# FRONT-UNIT-WIDE.net
KiCad netlist of a schematic drawn in Altium Designer
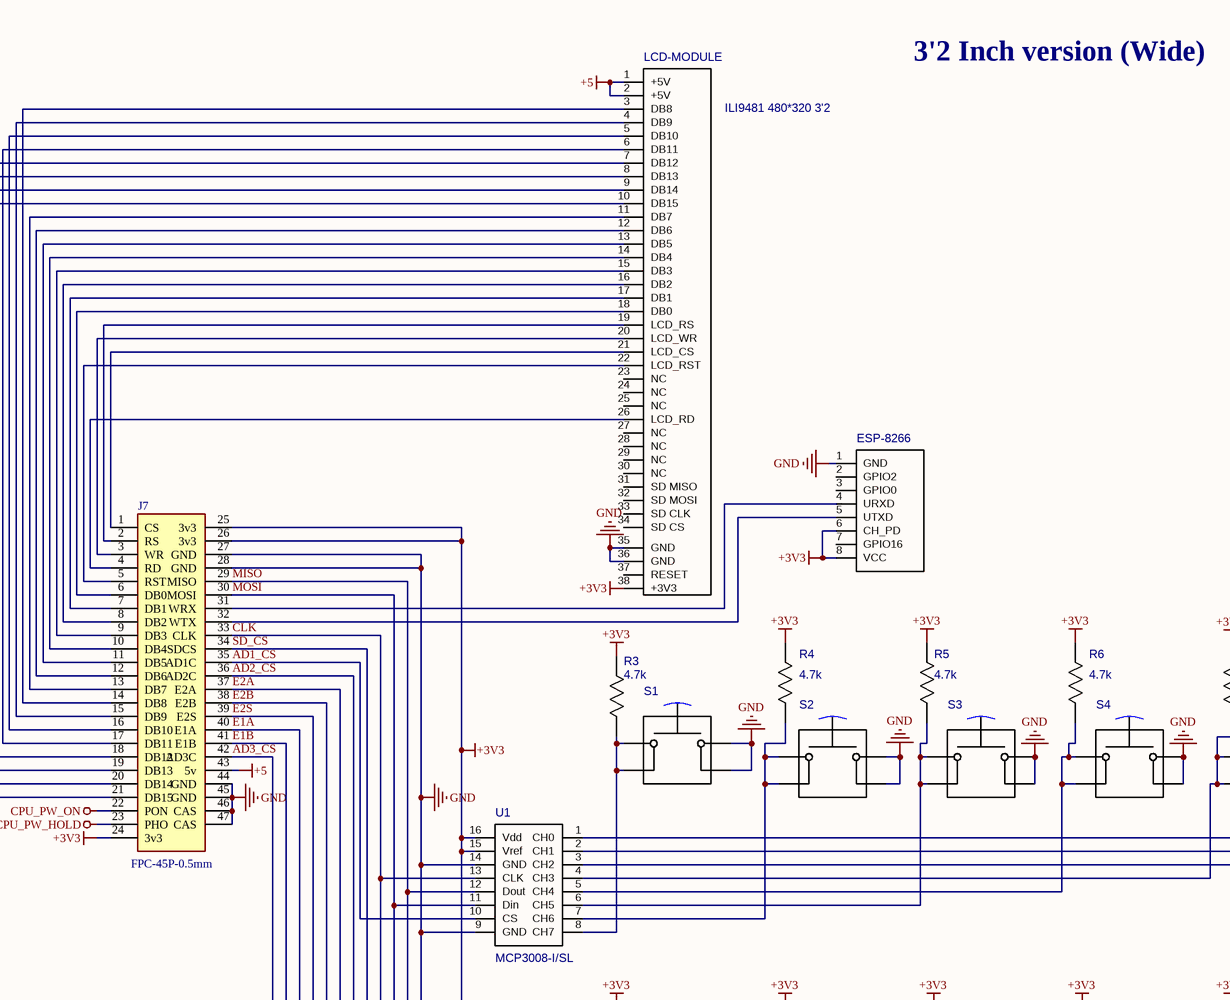
[diagram p0: FRONT-UNIT-WIDE.SCHDOC, top left]
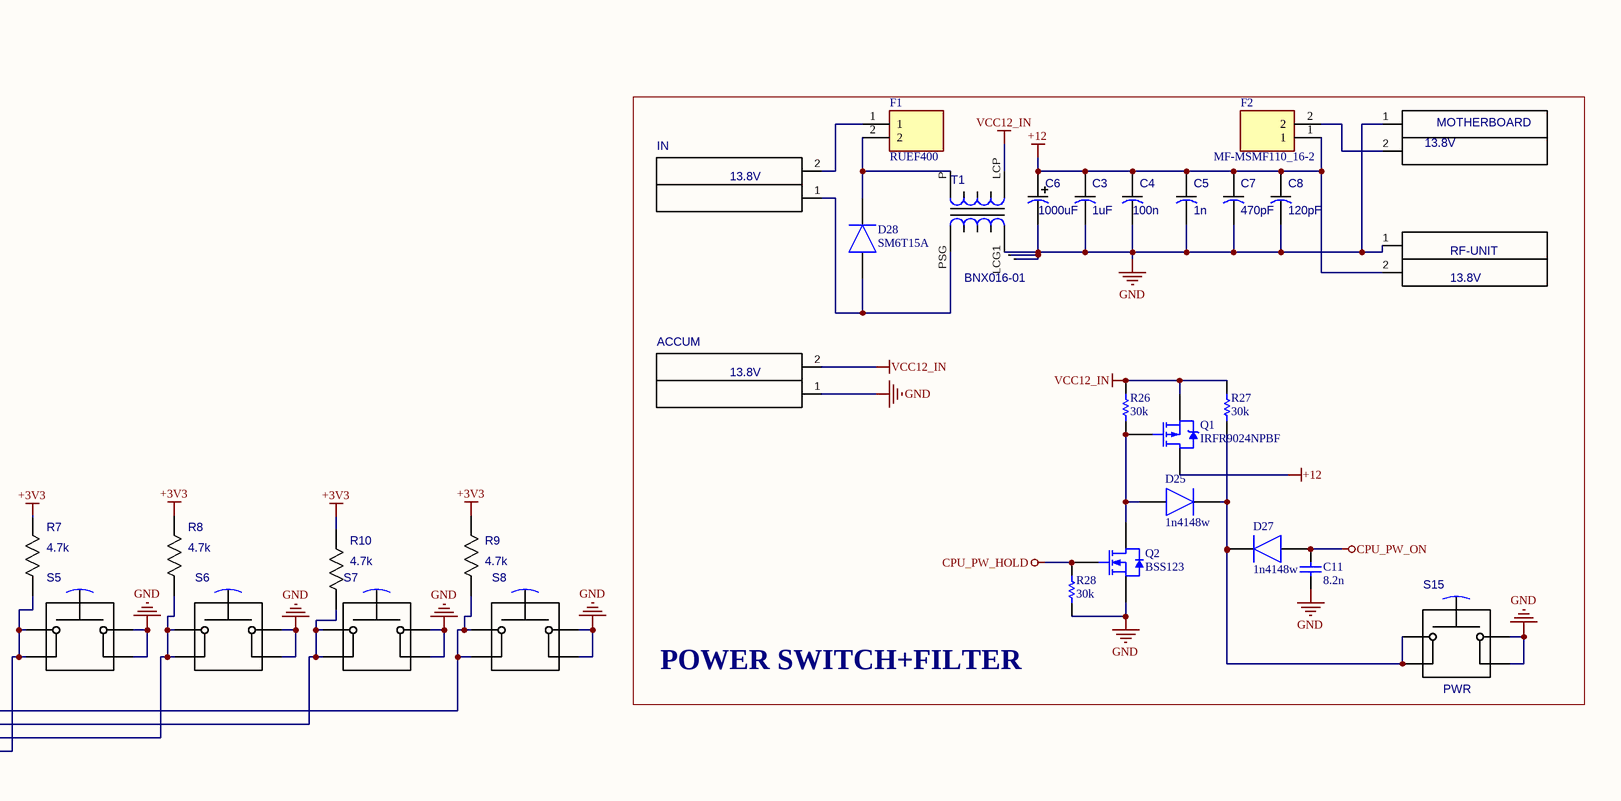
[diagram p1: FRONT-UNIT-WIDE.SCHDOC, top right]
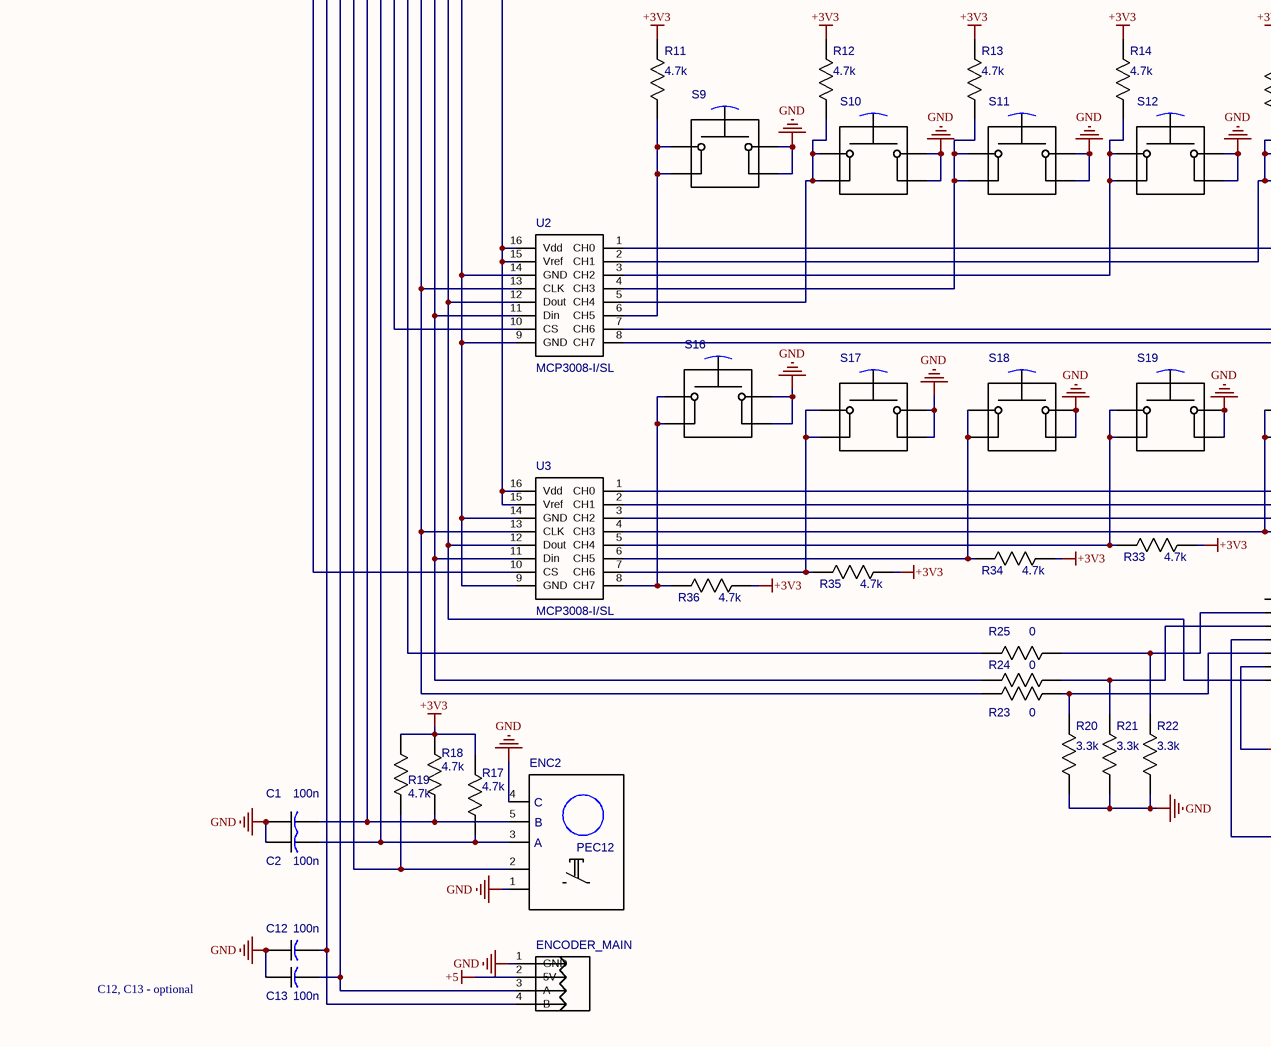
[diagram p2: FRONT-UNIT-WIDE.SCHDOC, bottom left]
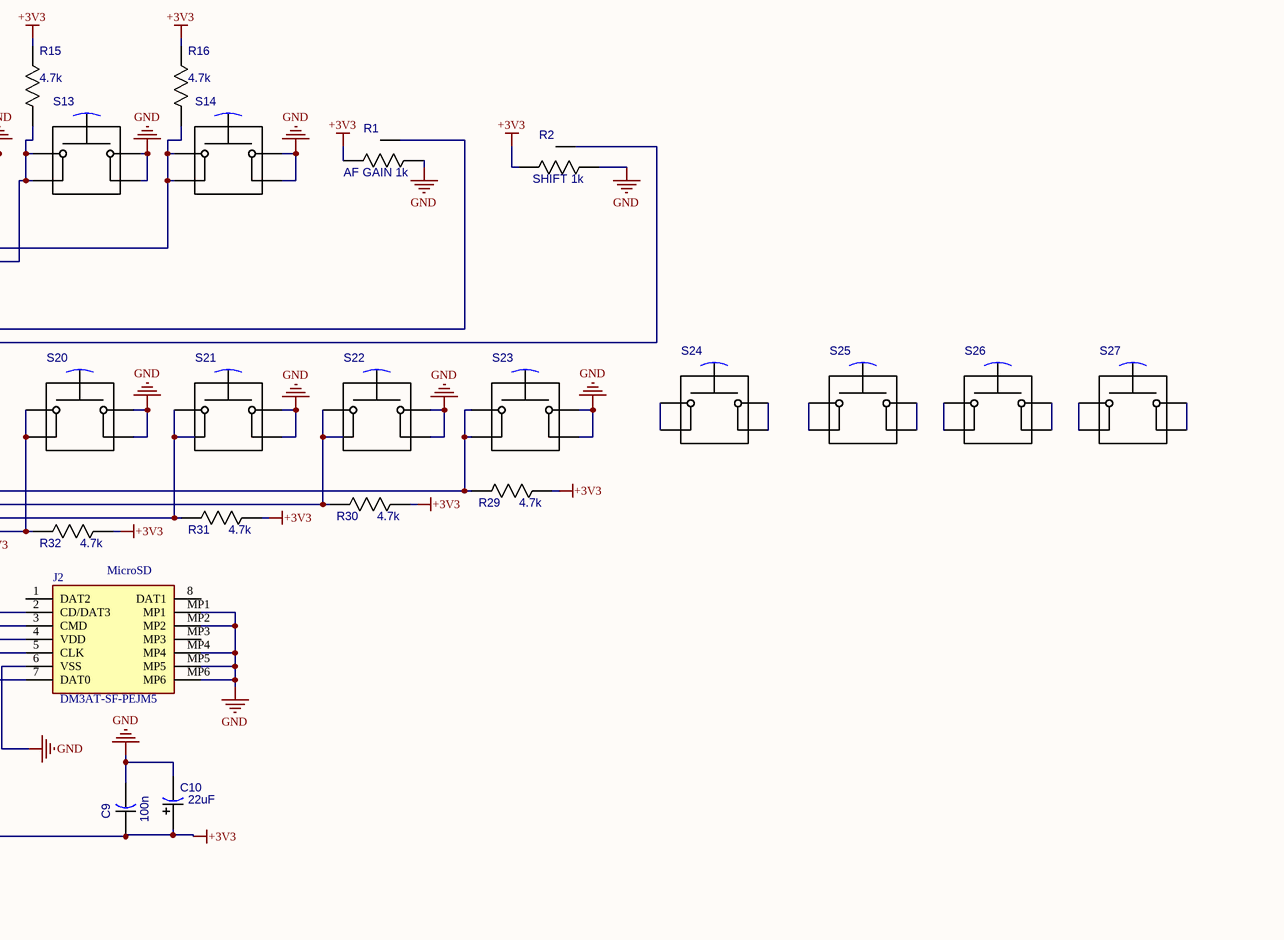
[diagram p3: FRONT-UNIT-WIDE.SCHDOC, bottom right]

(export (version "E")
  (design (tool "Eeschema 10.0.6"))
  (components
    (comp (ref "ACCUM")
      (value "13.8V")
      (footprint "JX2")
      (description "JX2")
      (libsource (lib "*") (part "JX2"))
    )
    (comp (ref "C1")
      (value "100n")
      (footprint "CAP_0805")
      (description "CAP_0805")
      (libsource (lib "*") (part "CAP_0805"))
    )
    (comp (ref "C2")
      (value "100n")
      (footprint "CAP_0805")
      (description "CAP_0805")
      (libsource (lib "*") (part "CAP_0805"))
    )
    (comp (ref "C3")
      (value "1uF")
      (footprint "CAP_1206")
      (description "CAP_1206")
      (libsource (lib "*") (part "CAP_1206"))
    )
    (comp (ref "C4")
      (value "100n")
      (footprint "CAP_1206")
      (description "CAP_1206")
      (libsource (lib "*") (part "CAP_1206"))
    )
    (comp (ref "C5")
      (value "1n")
      (footprint "CAP_1206")
      (description "CAP_1206")
      (libsource (lib "*") (part "CAP_1206"))
    )
    (comp (ref "C6")
      (value "1000uF")
      (footprint "CAP250RP")
      (description "CAP250RP")
      (libsource (lib "*") (part "CAP250RP"))
    )
    (comp (ref "C7")
      (value "470pF")
      (footprint "CAP_1206")
      (description "CAP_1206")
      (libsource (lib "*") (part "CAP_1206"))
    )
    (comp (ref "C8")
      (value "120pF")
      (footprint "CAP_1206")
      (description "CAP_1206")
      (libsource (lib "*") (part "CAP_1206"))
    )
    (comp (ref "C9")
      (value "100n")
      (footprint "CAP_0805")
      (description "CAP_0805")
      (libsource (lib "*") (part "CAP_0805"))
    )
    (comp (ref "C10")
      (value "22uF")
      (footprint "EEEFC_sizeB")
      (description "EEEFC_sizeB")
      (libsource (lib "*") (part "EEEFC_sizeB"))
    )
    (comp (ref "C11")
      (value "8.2n")
      (footprint "CAPC2013X94X50LL20T25")
      (description "CAP_1206")
      (fields
        (field (name "MANUFACTURER") "AVX Interconnect / Elco")
        (field (name "PART NUMBER") "08055C822KAT2A")
      )
      (libsource (lib "Altium Content Vault") (part "CAP"))
    )
    (comp (ref "C12")
      (value "100n")
      (footprint "CAP_0805")
      (description "CAP_0805")
      (libsource (lib "*") (part "CAP_0805"))
    )
    (comp (ref "C13")
      (value "100n")
      (footprint "CAP_0805")
      (description "CAP_0805")
      (libsource (lib "*") (part "CAP_0805"))
    )
    (comp (ref "D25")
      (value "1n4148w")
      (footprint "SamacSys:SOD3716X135N")
      (description "Diode")
      (libsource (lib "*") (part "1n4148w"))
    )
    (comp (ref "D27")
      (value "1n4148w")
      (footprint "SamacSys:SOD3716X135N")
      (description "Diode")
      (libsource (lib "*") (part "1n4148w"))
    )
    (comp (ref "D28")
      (value "SM6T15A")
      (footprint "SamacSys:SMBJ36CATR")
      (description "Diode")
      (fields (field (name "MOUSER PART NUMBER") "511-SM6T15A") (field (name "RS PART NUMBER") "4864915P"))
      (libsource (lib "*") (part "SM6T15A"))
    )
    (comp (ref "ENC2") (value "PEC12") (footprint "PEC12") (libsource (lib "*") (part "PEC12")))
    (comp (ref "ENCODER_MAIN")
      (value "OPTICAL ENCODER")
      (footprint "644456-4")
      (libsource (lib "*") (part "644456-4"))
    )
    (comp (ref "ESP-8266")
      (value "ESP-01 ESP8266")
      (footprint "ESP-01 ESP8266")
      (libsource (lib "*") (part "ESP-01 ESP8266"))
    )
    (comp (ref "F1")
      (value "RUEF400")
      (footprint "SamacSys:RUEF400")
      (description "Fuse")
      (fields (field (name "MOUSER PART NUMBER") "650-RUEF400") (field (name "RS PART NUMBER") "5176837P"))
      (libsource (lib "*") (part "RUEF400"))
    )
    (comp (ref "F2")
      (value "MF-MSMF110_16-2")
      (footprint "SamacSys:FUSC4632X85N")
      (description "Fuse")
      (fields
        (field (name "MANUFACTURER_PART_NUMBER") "MF-MSMF110/16-2")
        (field (name "MOUSER PART NUMBER") "652-MF-MSMF110/16-2")
      )
      (libsource (lib "*") (part "MF-MSMF110_16-2"))
    )
    (comp (ref "IN") (value "13.8V") (footprint "JX2") (description "JX2") (libsource (lib "*") (part "JX2")))
    (comp (ref "J2")
      (value "DM3AT-SF-PEJM5")
      (footprint "SamacSys:DM3ATSFPEJM5")
      (description "Connector")
      (libsource (lib "*") (part "DM3AT-SF-PEJM5"))
    )
    (comp (ref "J7")
      (value "FPC-45P-0.5mm")
      (footprint "FRONT-UNIT-WIDE:FH12S45S05SH60")
      (description "Connector")
      (fields
        (field (name "MANUFACTURER_PART_NUMBER") "FH12S-45S-0.5SH(55)")
        (field (name "MOUSER PART NUMBER") "798-FH12S-45S-05SH55")
      )
      (libsource (lib "*") (part "FH12S-45S-0.5SH_55_"))
    )
    (comp (ref "LCD-MODULE")
      (value "ILI9481 480*320 3'2")
      (footprint "LCD-MODULE-3.2-480-320")
      (description "LCD-MODULE_3'2_480х320")
      (libsource (lib "FRONT-UNIT") (part "LCD-MODULE_3'2_480х320"))
    )
    (comp (ref "MOTHERBOARD")
      (value "13.8V")
      (footprint "JX2")
      (description "JX2")
      (libsource (lib "*") (part "JX2"))
    )
    (comp (ref "Q1")
      (value "IRFR9024NPBF")
      (footprint "ONSC-DPAK-3-369C-01_V")
      (description "IRFR9024NPBF, Транзистор, Р-канал 55В 11А")
      (fields (field (name "MANUFACTURER") "On Semiconductor") (field (name "PARTNUMBER") "NTD2955G"))
      (libsource (lib "Altium Content Vault") (part "ONSC-PMOS-G1S3D4-3_B"))
    )
    (comp (ref "Q2")
      (value "BSS123")
      (footprint "FAIR-SOT23-3_V")
      (fields (field (name "MANUFACTURER") "Fairchild"))
      (libsource (lib "Altium Content Vault") (part "NEMOS-GSD-3"))
    )
    (comp (ref "R1")
      (value "AF GAIN 1k")
      (footprint "PTV09")
      (description "Adjustable Resistor PTV09")
      (fields (field (name "Comment") "ptv09a-4225f-b102"))
      (libsource (lib "*") (part "PTV09"))
    )
    (comp (ref "R2")
      (value "SHIFT 1k")
      (footprint "PTV09")
      (description "Adjustable Resistor PTV09")
      (fields (field (name "Comment") "ptv09a-4225f-b102"))
      (libsource (lib "*") (part "PTV09"))
    )
    (comp (ref "R3")
      (value "4.7k")
      (footprint "RES_0805")
      (description "RES_0805")
      (libsource (lib "*") (part "RES_0805"))
    )
    (comp (ref "R4")
      (value "4.7k")
      (footprint "RES_0805")
      (description "RES_0805")
      (libsource (lib "*") (part "RES_0805"))
    )
    (comp (ref "R5")
      (value "4.7k")
      (footprint "RES_0805")
      (description "RES_0805")
      (libsource (lib "*") (part "RES_0805"))
    )
    (comp (ref "R6")
      (value "4.7k")
      (footprint "RES_0805")
      (description "RES_0805")
      (libsource (lib "*") (part "RES_0805"))
    )
    (comp (ref "R7")
      (value "4.7k")
      (footprint "RES_0805")
      (description "RES_0805")
      (libsource (lib "*") (part "RES_0805"))
    )
    (comp (ref "R8")
      (value "4.7k")
      (footprint "RES_0805")
      (description "RES_0805")
      (libsource (lib "*") (part "RES_0805"))
    )
    (comp (ref "R9")
      (value "4.7k")
      (footprint "RES_0805")
      (description "RES_0805")
      (libsource (lib "*") (part "RES_0805"))
    )
    (comp (ref "R10")
      (value "4.7k")
      (footprint "RES_0805")
      (description "RES_0805")
      (libsource (lib "*") (part "RES_0805"))
    )
    (comp (ref "R11")
      (value "4.7k")
      (footprint "RES_0805")
      (description "RES_0805")
      (libsource (lib "*") (part "RES_0805"))
    )
    (comp (ref "R12")
      (value "4.7k")
      (footprint "RES_0805")
      (description "RES_0805")
      (libsource (lib "*") (part "RES_0805"))
    )
    (comp (ref "R13")
      (value "4.7k")
      (footprint "RES_0805")
      (description "RES_0805")
      (libsource (lib "*") (part "RES_0805"))
    )
    (comp (ref "R14")
      (value "4.7k")
      (footprint "RES_0805")
      (description "RES_0805")
      (libsource (lib "*") (part "RES_0805"))
    )
    (comp (ref "R15")
      (value "4.7k")
      (footprint "RES_0805")
      (description "RES_0805")
      (libsource (lib "*") (part "RES_0805"))
    )
    (comp (ref "R16")
      (value "4.7k")
      (footprint "RES_0805")
      (description "RES_0805")
      (libsource (lib "*") (part "RES_0805"))
    )
    (comp (ref "R17")
      (value "4.7k")
      (footprint "RES_0805")
      (description "RES_0805")
      (libsource (lib "*") (part "RES_0805"))
    )
    (comp (ref "R18")
      (value "4.7k")
      (footprint "RES_0805")
      (description "RES_0805")
      (libsource (lib "*") (part "RES_0805"))
    )
    (comp (ref "R19")
      (value "4.7k")
      (footprint "RES_0805")
      (description "RES_0805")
      (libsource (lib "*") (part "RES_0805"))
    )
    (comp (ref "R20")
      (value "3.3k")
      (footprint "RES_0805")
      (description "RES_0805")
      (libsource (lib "*") (part "RES_0805"))
    )
    (comp (ref "R21")
      (value "3.3k")
      (footprint "RES_0805")
      (description "RES_0805")
      (libsource (lib "*") (part "RES_0805"))
    )
    (comp (ref "R22")
      (value "3.3k")
      (footprint "RES_0805")
      (description "RES_0805")
      (libsource (lib "*") (part "RES_0805"))
    )
    (comp (ref "R23")
      (value "0")
      (footprint "RES_0805")
      (description "RES_0805")
      (libsource (lib "*") (part "RES_0805"))
    )
    (comp (ref "R24")
      (value "0")
      (footprint "RES_0805")
      (description "RES_0805")
      (libsource (lib "*") (part "RES_0805"))
    )
    (comp (ref "R25")
      (value "0")
      (footprint "RES_0805")
      (description "RES_0805")
      (libsource (lib "*") (part "RES_0805"))
    )
    (comp (ref "R26")
      (value "30k")
      (footprint "RESC2013X60X40NL20T25")
      (description "RES_0805")
      (fields (field (name "MANUFACTURER") "Panasonic") (field (name "PART NUMBER") "ERA-6AEB303V"))
      (libsource (lib "Altium Content Vault") (part "RES"))
    )
    (comp (ref "R27")
      (value "30k")
      (footprint "RESC2013X60X40NL20T25")
      (description "RES_0805")
      (fields (field (name "MANUFACTURER") "Panasonic") (field (name "PART NUMBER") "ERA-6AEB303V"))
      (libsource (lib "Altium Content Vault") (part "RES"))
    )
    (comp (ref "R28")
      (value "30k")
      (footprint "RESC2013X60X40NL20T25")
      (description "RES_0805")
      (fields (field (name "MANUFACTURER") "Panasonic") (field (name "PART NUMBER") "ERA-6AEB303V"))
      (libsource (lib "Altium Content Vault") (part "RES"))
    )
    (comp (ref "R29")
      (value "4.7k")
      (footprint "RES_0805")
      (description "RES_0805")
      (libsource (lib "*") (part "RES_0805"))
    )
    (comp (ref "R30")
      (value "4.7k")
      (footprint "RES_0805")
      (description "RES_0805")
      (libsource (lib "*") (part "RES_0805"))
    )
    (comp (ref "R31")
      (value "4.7k")
      (footprint "RES_0805")
      (description "RES_0805")
      (libsource (lib "*") (part "RES_0805"))
    )
    (comp (ref "R32")
      (value "4.7k")
      (footprint "RES_0805")
      (description "RES_0805")
      (libsource (lib "*") (part "RES_0805"))
    )
    (comp (ref "R33")
      (value "4.7k")
      (footprint "RES_0805")
      (description "RES_0805")
      (libsource (lib "*") (part "RES_0805"))
    )
    (comp (ref "R34")
      (value "4.7k")
      (footprint "RES_0805")
      (description "RES_0805")
      (libsource (lib "*") (part "RES_0805"))
    )
    (comp (ref "R35")
      (value "4.7k")
      (footprint "RES_0805")
      (description "RES_0805")
      (libsource (lib "*") (part "RES_0805"))
    )
    (comp (ref "R36")
      (value "4.7k")
      (footprint "RES_0805")
      (description "RES_0805")
      (libsource (lib "*") (part "RES_0805"))
    )
    (comp (ref "RF-UNIT")
      (value "13.8V")
      (footprint "JX2")
      (description "JX2")
      (libsource (lib "*") (part "JX2"))
    )
    (comp (ref "S1")
      (value "PTS645SK50LFS")
      (footprint "PTS645SK50LFS")
      (fields (field (name "LCSC PART #") "test"))
      (libsource (lib "*") (part "PTS645SK50LFS"))
    )
    (comp (ref "S2")
      (value "PTS645SK50LFS")
      (footprint "PTS645SK50LFS")
      (libsource (lib "*") (part "PTS645SK50LFS"))
    )
    (comp (ref "S3")
      (value "PTS645SK50LFS")
      (footprint "PTS645SK50LFS")
      (libsource (lib "*") (part "PTS645SK50LFS"))
    )
    (comp (ref "S4")
      (value "PTS645SK50LFS")
      (footprint "PTS645SK50LFS")
      (libsource (lib "*") (part "PTS645SK50LFS"))
    )
    (comp (ref "S5")
      (value "PTS645SK50LFS")
      (footprint "PTS645SK50LFS")
      (libsource (lib "*") (part "PTS645SK50LFS"))
    )
    (comp (ref "S6")
      (value "PTS645SK50LFS")
      (footprint "PTS645SK50LFS")
      (libsource (lib "*") (part "PTS645SK50LFS"))
    )
    (comp (ref "S7")
      (value "PTS645SK50LFS")
      (footprint "PTS645SK50LFS")
      (libsource (lib "*") (part "PTS645SK50LFS"))
    )
    (comp (ref "S8")
      (value "PTS645SK50LFS")
      (footprint "PTS645SK50LFS")
      (libsource (lib "*") (part "PTS645SK50LFS"))
    )
    (comp (ref "S9")
      (value "PTS645SK50LFS")
      (footprint "PTS645SK50LFS")
      (libsource (lib "*") (part "PTS645SK50LFS"))
    )
    (comp (ref "S10")
      (value "PTS645SK50LFS")
      (footprint "PTS645SK50LFS")
      (libsource (lib "*") (part "PTS645SK50LFS"))
    )
    (comp (ref "S11")
      (value "PTS645SK50LFS")
      (footprint "PTS645SK50LFS")
      (libsource (lib "*") (part "PTS645SK50LFS"))
    )
    (comp (ref "S12")
      (value "PTS645SK50LFS")
      (footprint "PTS645SK50LFS")
      (libsource (lib "*") (part "PTS645SK50LFS"))
    )
    (comp (ref "S13")
      (value "PTS645SK50LFS")
      (footprint "PTS645SK50LFS")
      (libsource (lib "*") (part "PTS645SK50LFS"))
    )
    (comp (ref "S14")
      (value "PTS645SK50LFS")
      (footprint "PTS645SK50LFS")
      (libsource (lib "*") (part "PTS645SK50LFS"))
    )
    (comp (ref "S15")
      (value "PWR")
      (footprint "PTS645SK50LFS")
      (description "PTS645SK50LFS")
      (libsource (lib "*") (part "PTS645SK50LFS"))
    )
    (comp (ref "S16")
      (value "PTS645SK50LFS")
      (footprint "PTS645SK50LFS")
      (libsource (lib "*") (part "PTS645SK50LFS"))
    )
    (comp (ref "S17")
      (value "PTS645SK50LFS")
      (footprint "PTS645SK50LFS")
      (libsource (lib "*") (part "PTS645SK50LFS"))
    )
    (comp (ref "S18")
      (value "PTS645SK50LFS")
      (footprint "PTS645SK50LFS")
      (libsource (lib "*") (part "PTS645SK50LFS"))
    )
    (comp (ref "S19")
      (value "PTS645SK50LFS")
      (footprint "PTS645SK50LFS")
      (libsource (lib "*") (part "PTS645SK50LFS"))
    )
    (comp (ref "S20")
      (value "PTS645SK50LFS")
      (footprint "PTS645SK50LFS")
      (libsource (lib "*") (part "PTS645SK50LFS"))
    )
    (comp (ref "S21")
      (value "PTS645SK50LFS")
      (footprint "PTS645SK50LFS")
      (libsource (lib "*") (part "PTS645SK50LFS"))
    )
    (comp (ref "S22")
      (value "PTS645SK50LFS")
      (footprint "PTS645SK50LFS")
      (libsource (lib "*") (part "PTS645SK50LFS"))
    )
    (comp (ref "S23")
      (value "PTS645SK50LFS")
      (footprint "PTS645SK50LFS")
      (libsource (lib "*") (part "PTS645SK50LFS"))
    )
    (comp (ref "S24")
      (value "PTS645SK50LFS")
      (footprint "PTS645SK50LFS")
      (libsource (lib "*") (part "PTS645SK50LFS"))
    )
    (comp (ref "S25")
      (value "PTS645SK50LFS")
      (footprint "PTS645SK50LFS")
      (libsource (lib "*") (part "PTS645SK50LFS"))
    )
    (comp (ref "S26")
      (value "PTS645SK50LFS")
      (footprint "PTS645SK50LFS")
      (libsource (lib "*") (part "PTS645SK50LFS"))
    )
    (comp (ref "S27")
      (value "PTS645SK50LFS")
      (footprint "PTS645SK50LFS")
      (libsource (lib "*") (part "PTS645SK50LFS"))
    )
    (comp (ref "T1")
      (value "BNX016-01")
      (footprint "TRANSF_ICORE")
      (libsource (lib "*") (part "TRANSF_ICORE"))
    )
    (comp (ref "U1")
      (value "MCP3008-I/SL")
      (footprint "MCP3008-I/SL")
      (libsource (lib "*") (part "MCP3008-I/SL"))
    )
    (comp (ref "U2")
      (value "MCP3008-I/SL")
      (footprint "MCP3008-I/SL")
      (libsource (lib "*") (part "MCP3008-I/SL"))
    )
    (comp (ref "U3")
      (value "MCP3008-I/SL")
      (footprint "MCP3008-I/SL")
      (libsource (lib "*") (part "MCP3008-I/SL"))
    )
  )
  (nets
    (net (code "1") (name "+3V3") (class "Default")
      (node (ref "C10") (pin "1") (pinfunction "PLUS_1") (pintype "passive"))
      (node (ref "C9") (pin "1") (pinfunction "1_1") (pintype "passive"))
      (node (ref "ESP-8266") (pin "6") (pinfunction "CH_PD_6") (pintype "passive"))
      (node (ref "ESP-8266") (pin "8") (pinfunction "VCC_8") (pintype "passive"))
      (node (ref "J2") (pin "4") (pinfunction "VDD_4") (pintype "passive"))
      (node (ref "J7") (pin "24") (pinfunction "3v3_24") (pintype "passive"))
      (node (ref "J7") (pin "25") (pinfunction "3v3_25") (pintype "passive"))
      (node (ref "J7") (pin "26") (pinfunction "3v3_26") (pintype "passive"))
      (node (ref "LCD-MODULE") (pin "38") (pinfunction "+3V3_38") (pintype "passive"))
      (node (ref "R1") (pin "1") (pinfunction "CW_1") (pintype "passive"))
      (node (ref "R10") (pin "2") (pinfunction "2_2") (pintype "passive"))
      (node (ref "R11") (pin "2") (pinfunction "2_2") (pintype "passive"))
      (node (ref "R12") (pin "2") (pinfunction "2_2") (pintype "passive"))
      (node (ref "R13") (pin "2") (pinfunction "2_2") (pintype "passive"))
      (node (ref "R14") (pin "2") (pinfunction "2_2") (pintype "passive"))
      (node (ref "R15") (pin "2") (pinfunction "2_2") (pintype "passive"))
      (node (ref "R16") (pin "2") (pinfunction "2_2") (pintype "passive"))
      (node (ref "R17") (pin "2") (pinfunction "2_2") (pintype "passive"))
      (node (ref "R18") (pin "2") (pinfunction "2_2") (pintype "passive"))
      (node (ref "R19") (pin "2") (pinfunction "2_2") (pintype "passive"))
      (node (ref "R2") (pin "1") (pinfunction "CW_1") (pintype "passive"))
      (node (ref "R29") (pin "2") (pinfunction "2_2") (pintype "passive"))
      (node (ref "R3") (pin "2") (pinfunction "2_2") (pintype "passive"))
      (node (ref "R30") (pin "2") (pinfunction "2_2") (pintype "passive"))
      (node (ref "R31") (pin "2") (pinfunction "2_2") (pintype "passive"))
      (node (ref "R32") (pin "2") (pinfunction "2_2") (pintype "passive"))
      (node (ref "R33") (pin "2") (pinfunction "2_2") (pintype "passive"))
      (node (ref "R34") (pin "2") (pinfunction "2_2") (pintype "passive"))
      (node (ref "R35") (pin "2") (pinfunction "2_2") (pintype "passive"))
      (node (ref "R36") (pin "2") (pinfunction "2_2") (pintype "passive"))
      (node (ref "R4") (pin "2") (pinfunction "2_2") (pintype "passive"))
      (node (ref "R5") (pin "2") (pinfunction "2_2") (pintype "passive"))
      (node (ref "R6") (pin "2") (pinfunction "2_2") (pintype "passive"))
      (node (ref "R7") (pin "2") (pinfunction "2_2") (pintype "passive"))
      (node (ref "R8") (pin "2") (pinfunction "2_2") (pintype "passive"))
      (node (ref "R9") (pin "2") (pinfunction "2_2") (pintype "passive"))
      (node (ref "U1") (pin "15") (pinfunction "Vref_15") (pintype "passive"))
      (node (ref "U1") (pin "16") (pinfunction "Vdd_16") (pintype "passive"))
      (node (ref "U2") (pin "15") (pinfunction "Vref_15") (pintype "passive"))
      (node (ref "U2") (pin "16") (pinfunction "Vdd_16") (pintype "passive"))
      (node (ref "U3") (pin "15") (pinfunction "Vref_15") (pintype "passive"))
      (node (ref "U3") (pin "16") (pinfunction "Vdd_16") (pintype "passive"))
    )
    (net (code "2") (name "+5") (class "Default")
      (node (ref "ENCODER_MAIN") (pin "2") (pinfunction "5V_2") (pintype "passive"))
      (node (ref "J7") (pin "43") (pinfunction "5v_43") (pintype "passive"))
      (node (ref "LCD-MODULE") (pin "1") (pinfunction "+5V_1") (pintype "passive"))
      (node (ref "LCD-MODULE") (pin "2") (pinfunction "+5V_2") (pintype "passive"))
    )
    (net (code "3") (name "+12") (class "Default")
      (node (ref "C3") (pin "1") (pinfunction "1_1") (pintype "passive"))
      (node (ref "C4") (pin "1") (pinfunction "1_1") (pintype "passive"))
      (node (ref "C5") (pin "1") (pinfunction "1_1") (pintype "passive"))
      (node (ref "C6") (pin "1") (pinfunction "PLUS_1") (pintype "passive"))
      (node (ref "C7") (pin "1") (pinfunction "1_1") (pintype "passive"))
      (node (ref "C8") (pin "1") (pinfunction "1_1") (pintype "passive"))
      (node (ref "F2") (pin "1") (pinfunction "1_1") (pintype "passive"))
      (node (ref "Q1") (pin "4") (pinfunction "D_4") (pintype "passive"))
      (node (ref "RF-UNIT") (pin "2") (pinfunction "2_2") (pintype "passive"))
    )
    (net (code "4") (name "/AD1_CS") (class "Default")
      (node (ref "J7") (pin "35") (pinfunction "AD1C_35") (pintype "passive"))
      (node (ref "U1") (pin "10") (pinfunction "CS_10") (pintype "passive"))
    )
    (net (code "5") (name "/AD2_CS") (class "Default")
      (node (ref "J7") (pin "36") (pinfunction "AD2C_36") (pintype "passive"))
      (node (ref "U2") (pin "10") (pinfunction "CS_10") (pintype "passive"))
    )
    (net (code "6") (name "/AD3_CS") (class "Default")
      (node (ref "J7") (pin "42") (pinfunction "AD3C_42") (pintype "passive"))
      (node (ref "U3") (pin "10") (pinfunction "CS_10") (pintype "passive"))
    )
    (net (code "7") (name "/CLK") (class "Default")
      (node (ref "J7") (pin "33") (pinfunction "CLK_33") (pintype "passive"))
      (node (ref "R23") (pin "2") (pinfunction "2_2") (pintype "passive"))
      (node (ref "U1") (pin "13") (pinfunction "CLK_13") (pintype "passive"))
      (node (ref "U2") (pin "13") (pinfunction "CLK_13") (pintype "passive"))
      (node (ref "U3") (pin "13") (pinfunction "CLK_13") (pintype "passive"))
    )
    (net (code "8") (name "/E1A") (class "Default")
      (node (ref "C13") (pin "2") (pinfunction "2_2") (pintype "passive"))
      (node (ref "ENCODER_MAIN") (pin "3") (pinfunction "A_3") (pintype "passive"))
      (node (ref "J7") (pin "40") (pinfunction "E1A_40") (pintype "passive"))
    )
    (net (code "9") (name "/E1B") (class "Default")
      (node (ref "C12") (pin "2") (pinfunction "2_2") (pintype "passive"))
      (node (ref "ENCODER_MAIN") (pin "4") (pinfunction "B_4") (pintype "passive"))
      (node (ref "J7") (pin "41") (pinfunction "E1B_41") (pintype "passive"))
    )
    (net (code "10") (name "/E2A") (class "Default")
      (node (ref "C2") (pin "2") (pinfunction "2_2") (pintype "passive"))
      (node (ref "ENC2") (pin "3") (pinfunction "A_3") (pintype "passive"))
      (node (ref "J7") (pin "37") (pinfunction "E2A_37") (pintype "passive"))
      (node (ref "R17") (pin "1") (pinfunction "1_1") (pintype "passive"))
    )
    (net (code "11") (name "/E2B") (class "Default")
      (node (ref "C1") (pin "2") (pinfunction "2_2") (pintype "passive"))
      (node (ref "ENC2") (pin "5") (pinfunction "B_5") (pintype "passive"))
      (node (ref "J7") (pin "38") (pinfunction "E2B_38") (pintype "passive"))
      (node (ref "R18") (pin "1") (pinfunction "1_1") (pintype "passive"))
    )
    (net (code "12") (name "/E2S") (class "Default")
      (node (ref "ENC2") (pin "2") (pinfunction "2_2") (pintype "passive"))
      (node (ref "J7") (pin "39") (pinfunction "E2S_39") (pintype "passive"))
      (node (ref "R19") (pin "1") (pinfunction "1_1") (pintype "passive"))
    )
    (net (code "13") (name "/MISO") (class "Default")
      (node (ref "J2") (pin "7") (pinfunction "DAT0_7") (pintype "passive"))
      (node (ref "J7") (pin "29") (pinfunction "MISO_29") (pintype "passive"))
      (node (ref "U1") (pin "12") (pinfunction "Dout_12") (pintype "passive"))
      (node (ref "U2") (pin "12") (pinfunction "Dout_12") (pintype "passive"))
      (node (ref "U3") (pin "12") (pinfunction "Dout_12") (pintype "passive"))
    )
    (net (code "14") (name "/MOSI") (class "Default")
      (node (ref "J7") (pin "30") (pinfunction "MOSI_30") (pintype "passive"))
      (node (ref "R24") (pin "2") (pinfunction "2_2") (pintype "passive"))
      (node (ref "U1") (pin "11") (pinfunction "Din_11") (pintype "passive"))
      (node (ref "U2") (pin "11") (pinfunction "Din_11") (pintype "passive"))
      (node (ref "U3") (pin "11") (pinfunction "Din_11") (pintype "passive"))
    )
    (net (code "15") (name "/SD_CS") (class "Default")
      (node (ref "J7") (pin "34") (pinfunction "SDCS_34") (pintype "passive"))
      (node (ref "R25") (pin "2") (pinfunction "2_2") (pintype "passive"))
    )
    (net (code "16") (name "CPU_PW_HOLD") (class "Default")
      (node (ref "J7") (pin "23") (pinfunction "PHO_23") (pintype "passive"))
      (node (ref "Q2") (pin "1") (pinfunction "G_1") (pintype "passive"))
      (node (ref "R28") (pin "2") (pinfunction "2_2") (pintype "passive"))
    )
    (net (code "17") (name "CPU_PW_ON") (class "Default")
      (node (ref "C11") (pin "2") (pinfunction "2_2") (pintype "passive"))
      (node (ref "D27") (pin "2") (pinfunction "A_2") (pintype "passive"))
      (node (ref "J7") (pin "22") (pinfunction "PON_22") (pintype "passive"))
    )
    (net (code "18") (name "GND") (class "Default")
      (node (ref "ACCUM") (pin "1") (pinfunction "1_1") (pintype "passive"))
      (node (ref "C1") (pin "1") (pinfunction "1_1") (pintype "passive"))
      (node (ref "C10") (pin "2") (pinfunction "MINUS_2") (pintype "passive"))
      (node (ref "C11") (pin "1") (pinfunction "1_1") (pintype "passive"))
      (node (ref "C12") (pin "1") (pinfunction "1_1") (pintype "passive"))
      (node (ref "C13") (pin "1") (pinfunction "1_1") (pintype "passive"))
      (node (ref "C2") (pin "1") (pinfunction "1_1") (pintype "passive"))
      (node (ref "C3") (pin "2") (pinfunction "2_2") (pintype "passive"))
      (node (ref "C4") (pin "2") (pinfunction "2_2") (pintype "passive"))
      (node (ref "C5") (pin "2") (pinfunction "2_2") (pintype "passive"))
      (node (ref "C6") (pin "2") (pinfunction "MINUS_2") (pintype "passive"))
      (node (ref "C7") (pin "2") (pinfunction "2_2") (pintype "passive"))
      (node (ref "C8") (pin "2") (pinfunction "2_2") (pintype "passive"))
      (node (ref "C9") (pin "2") (pinfunction "2_2") (pintype "passive"))
      (node (ref "ENC2") (pin "1") (pinfunction "1_1") (pintype "passive"))
      (node (ref "ENC2") (pin "4") (pinfunction "C_4") (pintype "passive"))
      (node (ref "ENCODER_MAIN") (pin "1") (pinfunction "GND_1") (pintype "passive"))
      (node (ref "ESP-8266") (pin "1") (pinfunction "GND_1") (pintype "passive"))
      (node (ref "J2") (pin "6") (pinfunction "VSS_6") (pintype "passive"))
      (node (ref "J2") (pin "MP1") (pinfunction "MP1_MP1") (pintype "passive"))
      (node (ref "J2") (pin "MP2") (pinfunction "MP2_MP2") (pintype "passive"))
      (node (ref "J2") (pin "MP4") (pinfunction "MP4_MP4") (pintype "passive"))
      (node (ref "J2") (pin "MP5") (pinfunction "MP5_MP5") (pintype "passive"))
      (node (ref "J2") (pin "MP6") (pinfunction "MP6_MP6") (pintype "passive"))
      (node (ref "J7") (pin "27") (pinfunction "GND_27") (pintype "passive"))
      (node (ref "J7") (pin "28") (pinfunction "GND_28") (pintype "passive"))
      (node (ref "J7") (pin "44") (pinfunction "GND_44") (pintype "passive"))
      (node (ref "J7") (pin "45") (pinfunction "GND_45") (pintype "passive"))
      (node (ref "J7") (pin "46") (pinfunction "CAS_46") (pintype "passive"))
      (node (ref "J7") (pin "47") (pinfunction "CAS_47") (pintype "passive"))
      (node (ref "LCD-MODULE") (pin "35") (pinfunction "GND_35") (pintype "passive"))
      (node (ref "LCD-MODULE") (pin "36") (pinfunction "GND_36") (pintype "passive"))
      (node (ref "MOTHERBOARD") (pin "1") (pinfunction "1_1") (pintype "passive"))
      (node (ref "Q2") (pin "2") (pinfunction "S_2") (pintype "passive"))
      (node (ref "R1") (pin "3") (pinfunction "CCW_3") (pintype "passive"))
      (node (ref "R2") (pin "3") (pinfunction "CCW_3") (pintype "passive"))
      (node (ref "R20") (pin "1") (pinfunction "1_1") (pintype "passive"))
      (node (ref "R21") (pin "1") (pinfunction "1_1") (pintype "passive"))
      (node (ref "R22") (pin "1") (pinfunction "1_1") (pintype "passive"))
      (node (ref "R28") (pin "1") (pinfunction "1_1") (pintype "passive"))
      (node (ref "RF-UNIT") (pin "1") (pinfunction "1_1") (pintype "passive"))
      (node (ref "S1") (pin "3") (pinfunction "B_3") (pintype "passive"))
      (node (ref "S1") (pin "4") (pinfunction "B_4") (pintype "passive"))
      (node (ref "S10") (pin "3") (pinfunction "B_3") (pintype "passive"))
      (node (ref "S10") (pin "4") (pinfunction "B_4") (pintype "passive"))
      (node (ref "S11") (pin "3") (pinfunction "B_3") (pintype "passive"))
      (node (ref "S11") (pin "4") (pinfunction "B_4") (pintype "passive"))
      (node (ref "S12") (pin "3") (pinfunction "B_3") (pintype "passive"))
      (node (ref "S12") (pin "4") (pinfunction "B_4") (pintype "passive"))
      (node (ref "S13") (pin "3") (pinfunction "B_3") (pintype "passive"))
      (node (ref "S13") (pin "4") (pinfunction "B_4") (pintype "passive"))
      (node (ref "S14") (pin "3") (pinfunction "B_3") (pintype "passive"))
      (node (ref "S14") (pin "4") (pinfunction "B_4") (pintype "passive"))
      (node (ref "S15") (pin "3") (pinfunction "B_3") (pintype "passive"))
      (node (ref "S15") (pin "4") (pinfunction "B_4") (pintype "passive"))
      (node (ref "S16") (pin "3") (pinfunction "B_3") (pintype "passive"))
      (node (ref "S16") (pin "4") (pinfunction "B_4") (pintype "passive"))
      (node (ref "S17") (pin "3") (pinfunction "B_3") (pintype "passive"))
      (node (ref "S17") (pin "4") (pinfunction "B_4") (pintype "passive"))
      (node (ref "S18") (pin "3") (pinfunction "B_3") (pintype "passive"))
      (node (ref "S18") (pin "4") (pinfunction "B_4") (pintype "passive"))
      (node (ref "S19") (pin "3") (pinfunction "B_3") (pintype "passive"))
      (node (ref "S19") (pin "4") (pinfunction "B_4") (pintype "passive"))
      (node (ref "S2") (pin "3") (pinfunction "B_3") (pintype "passive"))
      (node (ref "S2") (pin "4") (pinfunction "B_4") (pintype "passive"))
      (node (ref "S20") (pin "3") (pinfunction "B_3") (pintype "passive"))
      (node (ref "S20") (pin "4") (pinfunction "B_4") (pintype "passive"))
      (node (ref "S21") (pin "3") (pinfunction "B_3") (pintype "passive"))
      (node (ref "S21") (pin "4") (pinfunction "B_4") (pintype "passive"))
      (node (ref "S22") (pin "3") (pinfunction "B_3") (pintype "passive"))
      (node (ref "S22") (pin "4") (pinfunction "B_4") (pintype "passive"))
      (node (ref "S23") (pin "3") (pinfunction "B_3") (pintype "passive"))
      (node (ref "S23") (pin "4") (pinfunction "B_4") (pintype "passive"))
      (node (ref "S3") (pin "3") (pinfunction "B_3") (pintype "passive"))
      (node (ref "S3") (pin "4") (pinfunction "B_4") (pintype "passive"))
      (node (ref "S4") (pin "3") (pinfunction "B_3") (pintype "passive"))
      (node (ref "S4") (pin "4") (pinfunction "B_4") (pintype "passive"))
      (node (ref "S5") (pin "3") (pinfunction "B_3") (pintype "passive"))
      (node (ref "S5") (pin "4") (pinfunction "B_4") (pintype "passive"))
      (node (ref "S6") (pin "3") (pinfunction "B_3") (pintype "passive"))
      (node (ref "S6") (pin "4") (pinfunction "B_4") (pintype "passive"))
      (node (ref "S7") (pin "3") (pinfunction "B_3") (pintype "passive"))
      (node (ref "S7") (pin "4") (pinfunction "B_4") (pintype "passive"))
      (node (ref "S8") (pin "3") (pinfunction "B_3") (pintype "passive"))
      (node (ref "S8") (pin "4") (pinfunction "B_4") (pintype "passive"))
      (node (ref "S9") (pin "3") (pinfunction "B_3") (pintype "passive"))
      (node (ref "S9") (pin "4") (pinfunction "B_4") (pintype "passive"))
      (node (ref "T1") (pin "LCG1") (pinfunction "S2_LCG1") (pintype "passive"))
      (node (ref "T1") (pin "LCG2") (pinfunction "0_LCG2") (pintype "passive"))
      (node (ref "T1") (pin "LCG3") (pinfunction "0_LCG3") (pintype "passive"))
      (node (ref "U1") (pin "14") (pinfunction "GND_14") (pintype "passive"))
      (node (ref "U1") (pin "9") (pinfunction "GND_9") (pintype "passive"))
      (node (ref "U2") (pin "14") (pinfunction "GND_14") (pintype "passive"))
      (node (ref "U2") (pin "9") (pinfunction "GND_9") (pintype "passive"))
      (node (ref "U3") (pin "14") (pinfunction "GND_14") (pintype "passive"))
      (node (ref "U3") (pin "9") (pinfunction "GND_9") (pintype "passive"))
    )
    (net (code "19") (name "Net-(D25-A)") (class "Default")
      (node (ref "D25") (pin "2") (pinfunction "A_2") (pintype "passive"))
      (node (ref "Q1") (pin "1") (pinfunction "G_1") (pintype "passive"))
      (node (ref "Q2") (pin "3") (pinfunction "D_3") (pintype "passive"))
      (node (ref "R26") (pin "1") (pinfunction "1_1") (pintype "passive"))
    )
    (net (code "20") (name "Net-(D25-K)") (class "Default")
      (node (ref "D25") (pin "1") (pinfunction "K_1") (pintype "passive"))
      (node (ref "D27") (pin "1") (pinfunction "K_1") (pintype "passive"))
      (node (ref "R27") (pin "1") (pinfunction "1_1") (pintype "passive"))
      (node (ref "S15") (pin "1") (pinfunction "A_1") (pintype "passive"))
      (node (ref "S15") (pin "2") (pinfunction "A_2") (pintype "passive"))
    )
    (net (code "21") (name "Net-(D28-A)") (class "Default")
      (node (ref "D28") (pin "2") (pinfunction "A_2") (pintype "passive"))
      (node (ref "IN") (pin "1") (pinfunction "1_1") (pintype "passive"))
      (node (ref "T1") (pin "PSG") (pinfunction "S1_PSG") (pintype "passive"))
    )
    (net (code "22") (name "Net-(D28-K)") (class "Default")
      (node (ref "D28") (pin "1") (pinfunction "K_1") (pintype "passive"))
      (node (ref "F1") (pin "2") (pinfunction "2_2") (pintype "passive"))
      (node (ref "T1") (pin "P") (pinfunction "P1_P") (pintype "passive"))
    )
    (net (code "23") (name "Net-(ESP-8266-URXD)") (class "Default")
      (node (ref "ESP-8266") (pin "4") (pinfunction "URXD_4") (pintype "passive"))
      (node (ref "J7") (pin "31") (pinfunction "WRX_31") (pintype "passive"))
    )
    (net (code "24") (name "Net-(ESP-8266-UTXD)") (class "Default")
      (node (ref "ESP-8266") (pin "5") (pinfunction "UTXD_5") (pintype "passive"))
      (node (ref "J7") (pin "32") (pinfunction "WTX_32") (pintype "passive"))
    )
    (net (code "25") (name "Net-(F1-Pad1)") (class "Default")
      (node (ref "F1") (pin "1") (pinfunction "1_1") (pintype "passive"))
      (node (ref "IN") (pin "2") (pinfunction "2_2") (pintype "passive"))
    )
    (net (code "26") (name "Net-(F2-Pad2)") (class "Default")
      (node (ref "F2") (pin "2") (pinfunction "2_2") (pintype "passive"))
      (node (ref "MOTHERBOARD") (pin "2") (pinfunction "2_2") (pintype "passive"))
    )
    (net (code "27") (name "Net-(J2-CD{slash}DAT3)") (class "Default")
      (node (ref "J2") (pin "2") (pinfunction "CD/DAT3_2") (pintype "passive"))
      (node (ref "R22") (pin "2") (pinfunction "2_2") (pintype "passive"))
      (node (ref "R25") (pin "1") (pinfunction "1_1") (pintype "passive"))
    )
    (net (code "28") (name "Net-(J2-CLK)") (class "Default")
      (node (ref "J2") (pin "5") (pinfunction "CLK_5") (pintype "passive"))
      (node (ref "R20") (pin "2") (pinfunction "2_2") (pintype "passive"))
      (node (ref "R23") (pin "1") (pinfunction "1_1") (pintype "passive"))
    )
    (net (code "29") (name "Net-(J2-CMD)") (class "Default")
      (node (ref "J2") (pin "3") (pinfunction "CMD_3") (pintype "passive"))
      (node (ref "R21") (pin "2") (pinfunction "2_2") (pintype "passive"))
      (node (ref "R24") (pin "1") (pinfunction "1_1") (pintype "passive"))
    )
    (net (code "30") (name "Net-(J7-CS)") (class "Default")
      (node (ref "J7") (pin "1") (pinfunction "CS_1") (pintype "passive"))
      (node (ref "LCD-MODULE") (pin "21") (pinfunction "LCD_CS_21") (pintype "passive"))
    )
    (net (code "31") (name "Net-(J7-DB0)") (class "Default")
      (node (ref "J7") (pin "6") (pinfunction "DB0_6") (pintype "passive"))
      (node (ref "LCD-MODULE") (pin "18") (pinfunction "DB0_18") (pintype "passive"))
    )
    (net (code "32") (name "Net-(J7-DB1)") (class "Default")
      (node (ref "J7") (pin "7") (pinfunction "DB1_7") (pintype "passive"))
      (node (ref "LCD-MODULE") (pin "17") (pinfunction "DB1_17") (pintype "passive"))
    )
    (net (code "33") (name "Net-(J7-DB2)") (class "Default")
      (node (ref "J7") (pin "8") (pinfunction "DB2_8") (pintype "passive"))
      (node (ref "LCD-MODULE") (pin "16") (pinfunction "DB2_16") (pintype "passive"))
    )
    (net (code "34") (name "Net-(J7-DB3)") (class "Default")
      (node (ref "J7") (pin "9") (pinfunction "DB3_9") (pintype "passive"))
      (node (ref "LCD-MODULE") (pin "15") (pinfunction "DB3_15") (pintype "passive"))
    )
    (net (code "35") (name "Net-(J7-DB4)") (class "Default")
      (node (ref "J7") (pin "10") (pinfunction "DB4_10") (pintype "passive"))
      (node (ref "LCD-MODULE") (pin "14") (pinfunction "DB4_14") (pintype "passive"))
    )
    (net (code "36") (name "Net-(J7-DB5)") (class "Default")
      (node (ref "J7") (pin "11") (pinfunction "DB5_11") (pintype "passive"))
      (node (ref "LCD-MODULE") (pin "13") (pinfunction "DB5_13") (pintype "passive"))
    )
    (net (code "37") (name "Net-(J7-DB6)") (class "Default")
      (node (ref "J7") (pin "12") (pinfunction "DB6_12") (pintype "passive"))
      (node (ref "LCD-MODULE") (pin "12") (pinfunction "DB6_12") (pintype "passive"))
    )
    (net (code "38") (name "Net-(J7-DB7)") (class "Default")
      (node (ref "J7") (pin "13") (pinfunction "DB7_13") (pintype "passive"))
      (node (ref "LCD-MODULE") (pin "11") (pinfunction "DB7_11") (pintype "passive"))
    )
    (net (code "39") (name "Net-(J7-DB8)") (class "Default")
      (node (ref "J7") (pin "14") (pinfunction "DB8_14") (pintype "passive"))
      (node (ref "LCD-MODULE") (pin "3") (pinfunction "DB8_3") (pintype "passive"))
    )
    (net (code "40") (name "Net-(J7-DB9)") (class "Default")
      (node (ref "J7") (pin "15") (pinfunction "DB9_15") (pintype "passive"))
      (node (ref "LCD-MODULE") (pin "4") (pinfunction "DB9_4") (pintype "passive"))
    )
    (net (code "41") (name "Net-(J7-DB10)") (class "Default")
      (node (ref "J7") (pin "16") (pinfunction "DB10_16") (pintype "passive"))
      (node (ref "LCD-MODULE") (pin "5") (pinfunction "DB10_5") (pintype "passive"))
    )
    (net (code "42") (name "Net-(J7-DB11)") (class "Default")
      (node (ref "J7") (pin "17") (pinfunction "DB11_17") (pintype "passive"))
      (node (ref "LCD-MODULE") (pin "6") (pinfunction "DB11_6") (pintype "passive"))
    )
    (net (code "43") (name "Net-(J7-DB12)") (class "Default")
      (node (ref "J7") (pin "18") (pinfunction "DB12_18") (pintype "passive"))
      (node (ref "LCD-MODULE") (pin "7") (pinfunction "DB12_7") (pintype "passive"))
    )
    (net (code "44") (name "Net-(J7-DB13)") (class "Default")
      (node (ref "J7") (pin "19") (pinfunction "DB13_19") (pintype "passive"))
      (node (ref "LCD-MODULE") (pin "8") (pinfunction "DB13_8") (pintype "passive"))
    )
    (net (code "45") (name "Net-(J7-DB14)") (class "Default")
      (node (ref "J7") (pin "20") (pinfunction "DB14_20") (pintype "passive"))
      (node (ref "LCD-MODULE") (pin "9") (pinfunction "DB14_9") (pintype "passive"))
    )
    (net (code "46") (name "Net-(J7-DB15)") (class "Default")
      (node (ref "J7") (pin "21") (pinfunction "DB15_21") (pintype "passive"))
      (node (ref "LCD-MODULE") (pin "10") (pinfunction "DB15_10") (pintype "passive"))
    )
    (net (code "47") (name "Net-(J7-RD)") (class "Default")
      (node (ref "J7") (pin "4") (pinfunction "RD_4") (pintype "passive"))
      (node (ref "LCD-MODULE") (pin "26") (pinfunction "LCD_RD_26") (pintype "passive"))
    )
    (net (code "48") (name "Net-(J7-RS)") (class "Default")
      (node (ref "J7") (pin "2") (pinfunction "RS_2") (pintype "passive"))
      (node (ref "LCD-MODULE") (pin "19") (pinfunction "LCD_RS_19") (pintype "passive"))
    )
    (net (code "49") (name "Net-(J7-RST)") (class "Default")
      (node (ref "J7") (pin "5") (pinfunction "RST_5") (pintype "passive"))
      (node (ref "LCD-MODULE") (pin "22") (pinfunction "LCD_RST_22") (pintype "passive"))
    )
    (net (code "50") (name "Net-(J7-WR)") (class "Default")
      (node (ref "J7") (pin "3") (pinfunction "WR_3") (pintype "passive"))
      (node (ref "LCD-MODULE") (pin "20") (pinfunction "LCD_WR_20") (pintype "passive"))
    )
    (net (code "51") (name "Net-(R1-W)") (class "Default")
      (node (ref "R1") (pin "2") (pinfunction "W_2") (pintype "passive"))
      (node (ref "U2") (pin "7") (pinfunction "CH6_7") (pintype "passive"))
    )
    (net (code "52") (name "Net-(R2-W)") (class "Default")
      (node (ref "R2") (pin "2") (pinfunction "W_2") (pintype "passive"))
      (node (ref "U2") (pin "8") (pinfunction "CH7_8") (pintype "passive"))
    )
    (net (code "53") (name "Net-(S24-A-Pad1)") (class "Default")
      (node (ref "S24") (pin "1") (pinfunction "A_1") (pintype "passive"))
      (node (ref "S24") (pin "2") (pinfunction "A_2") (pintype "passive"))
    )
    (net (code "54") (name "Net-(S24-B-Pad3)") (class "Default")
      (node (ref "S24") (pin "3") (pinfunction "B_3") (pintype "passive"))
      (node (ref "S24") (pin "4") (pinfunction "B_4") (pintype "passive"))
    )
    (net (code "55") (name "Net-(S25-A-Pad1)") (class "Default")
      (node (ref "S25") (pin "1") (pinfunction "A_1") (pintype "passive"))
      (node (ref "S25") (pin "2") (pinfunction "A_2") (pintype "passive"))
    )
    (net (code "56") (name "Net-(S25-B-Pad3)") (class "Default")
      (node (ref "S25") (pin "3") (pinfunction "B_3") (pintype "passive"))
      (node (ref "S25") (pin "4") (pinfunction "B_4") (pintype "passive"))
    )
    (net (code "57") (name "Net-(S26-A-Pad1)") (class "Default")
      (node (ref "S26") (pin "1") (pinfunction "A_1") (pintype "passive"))
      (node (ref "S26") (pin "2") (pinfunction "A_2") (pintype "passive"))
    )
    (net (code "58") (name "Net-(S26-B-Pad3)") (class "Default")
      (node (ref "S26") (pin "3") (pinfunction "B_3") (pintype "passive"))
      (node (ref "S26") (pin "4") (pinfunction "B_4") (pintype "passive"))
    )
    (net (code "59") (name "Net-(S27-A-Pad1)") (class "Default")
      (node (ref "S27") (pin "1") (pinfunction "A_1") (pintype "passive"))
      (node (ref "S27") (pin "2") (pinfunction "A_2") (pintype "passive"))
    )
    (net (code "60") (name "Net-(S27-B-Pad3)") (class "Default")
      (node (ref "S27") (pin "3") (pinfunction "B_3") (pintype "passive"))
      (node (ref "S27") (pin "4") (pinfunction "B_4") (pintype "passive"))
    )
    (net (code "61") (name "Net-(U1-CH0)") (class "Default")
      (node (ref "R9") (pin "1") (pinfunction "1_1") (pintype "passive"))
      (node (ref "S8") (pin "1") (pinfunction "A_1") (pintype "passive"))
      (node (ref "S8") (pin "2") (pinfunction "A_2") (pintype "passive"))
      (node (ref "U1") (pin "1") (pinfunction "CH0_1") (pintype "passive"))
    )
    (net (code "62") (name "Net-(U1-CH1)") (class "Default")
      (node (ref "R10") (pin "1") (pinfunction "1_1") (pintype "passive"))
      (node (ref "S7") (pin "1") (pinfunction "A_1") (pintype "passive"))
      (node (ref "S7") (pin "2") (pinfunction "A_2") (pintype "passive"))
      (node (ref "U1") (pin "2") (pinfunction "CH1_2") (pintype "passive"))
    )
    (net (code "63") (name "Net-(U1-CH2)") (class "Default")
      (node (ref "R8") (pin "1") (pinfunction "1_1") (pintype "passive"))
      (node (ref "S6") (pin "1") (pinfunction "A_1") (pintype "passive"))
      (node (ref "S6") (pin "2") (pinfunction "A_2") (pintype "passive"))
      (node (ref "U1") (pin "3") (pinfunction "CH2_3") (pintype "passive"))
    )
    (net (code "64") (name "Net-(U1-CH3)") (class "Default")
      (node (ref "R7") (pin "1") (pinfunction "1_1") (pintype "passive"))
      (node (ref "S5") (pin "1") (pinfunction "A_1") (pintype "passive"))
      (node (ref "S5") (pin "2") (pinfunction "A_2") (pintype "passive"))
      (node (ref "U1") (pin "4") (pinfunction "CH3_4") (pintype "passive"))
    )
    (net (code "65") (name "Net-(U1-CH4)") (class "Default")
      (node (ref "R6") (pin "1") (pinfunction "1_1") (pintype "passive"))
      (node (ref "S4") (pin "1") (pinfunction "A_1") (pintype "passive"))
      (node (ref "S4") (pin "2") (pinfunction "A_2") (pintype "passive"))
      (node (ref "U1") (pin "5") (pinfunction "CH4_5") (pintype "passive"))
    )
    (net (code "66") (name "Net-(U1-CH5)") (class "Default")
      (node (ref "R5") (pin "1") (pinfunction "1_1") (pintype "passive"))
      (node (ref "S3") (pin "1") (pinfunction "A_1") (pintype "passive"))
      (node (ref "S3") (pin "2") (pinfunction "A_2") (pintype "passive"))
      (node (ref "U1") (pin "6") (pinfunction "CH5_6") (pintype "passive"))
    )
    (net (code "67") (name "Net-(U1-CH6)") (class "Default")
      (node (ref "R4") (pin "1") (pinfunction "1_1") (pintype "passive"))
      (node (ref "S2") (pin "1") (pinfunction "A_1") (pintype "passive"))
      (node (ref "S2") (pin "2") (pinfunction "A_2") (pintype "passive"))
      (node (ref "U1") (pin "7") (pinfunction "CH6_7") (pintype "passive"))
    )
    (net (code "68") (name "Net-(U1-CH7)") (class "Default")
      (node (ref "R3") (pin "1") (pinfunction "1_1") (pintype "passive"))
      (node (ref "S1") (pin "1") (pinfunction "A_1") (pintype "passive"))
      (node (ref "S1") (pin "2") (pinfunction "A_2") (pintype "passive"))
      (node (ref "U1") (pin "8") (pinfunction "CH7_8") (pintype "passive"))
    )
    (net (code "69") (name "Net-(U2-CH0)") (class "Default")
      (node (ref "R16") (pin "1") (pinfunction "1_1") (pintype "passive"))
      (node (ref "S14") (pin "1") (pinfunction "A_1") (pintype "passive"))
      (node (ref "S14") (pin "2") (pinfunction "A_2") (pintype "passive"))
      (node (ref "U2") (pin "1") (pinfunction "CH0_1") (pintype "passive"))
    )
    (net (code "70") (name "Net-(U2-CH1)") (class "Default")
      (node (ref "R15") (pin "1") (pinfunction "1_1") (pintype "passive"))
      (node (ref "S13") (pin "1") (pinfunction "A_1") (pintype "passive"))
      (node (ref "S13") (pin "2") (pinfunction "A_2") (pintype "passive"))
      (node (ref "U2") (pin "2") (pinfunction "CH1_2") (pintype "passive"))
    )
    (net (code "71") (name "Net-(U2-CH2)") (class "Default")
      (node (ref "R14") (pin "1") (pinfunction "1_1") (pintype "passive"))
      (node (ref "S12") (pin "1") (pinfunction "A_1") (pintype "passive"))
      (node (ref "S12") (pin "2") (pinfunction "A_2") (pintype "passive"))
      (node (ref "U2") (pin "3") (pinfunction "CH2_3") (pintype "passive"))
    )
    (net (code "72") (name "Net-(U2-CH3)") (class "Default")
      (node (ref "R13") (pin "1") (pinfunction "1_1") (pintype "passive"))
      (node (ref "S11") (pin "1") (pinfunction "A_1") (pintype "passive"))
      (node (ref "S11") (pin "2") (pinfunction "A_2") (pintype "passive"))
      (node (ref "U2") (pin "4") (pinfunction "CH3_4") (pintype "passive"))
    )
    (net (code "73") (name "Net-(U2-CH4)") (class "Default")
      (node (ref "R12") (pin "1") (pinfunction "1_1") (pintype "passive"))
      (node (ref "S10") (pin "1") (pinfunction "A_1") (pintype "passive"))
      (node (ref "S10") (pin "2") (pinfunction "A_2") (pintype "passive"))
      (node (ref "U2") (pin "5") (pinfunction "CH4_5") (pintype "passive"))
    )
    (net (code "74") (name "Net-(U2-CH5)") (class "Default")
      (node (ref "R11") (pin "1") (pinfunction "1_1") (pintype "passive"))
      (node (ref "S9") (pin "1") (pinfunction "A_1") (pintype "passive"))
      (node (ref "S9") (pin "2") (pinfunction "A_2") (pintype "passive"))
      (node (ref "U2") (pin "6") (pinfunction "CH5_6") (pintype "passive"))
    )
    (net (code "75") (name "Net-(U3-CH0)") (class "Default")
      (node (ref "R29") (pin "1") (pinfunction "1_1") (pintype "passive"))
      (node (ref "S23") (pin "1") (pinfunction "A_1") (pintype "passive"))
      (node (ref "S23") (pin "2") (pinfunction "A_2") (pintype "passive"))
      (node (ref "U3") (pin "1") (pinfunction "CH0_1") (pintype "passive"))
    )
    (net (code "76") (name "Net-(U3-CH1)") (class "Default")
      (node (ref "R30") (pin "1") (pinfunction "1_1") (pintype "passive"))
      (node (ref "S22") (pin "1") (pinfunction "A_1") (pintype "passive"))
      (node (ref "S22") (pin "2") (pinfunction "A_2") (pintype "passive"))
      (node (ref "U3") (pin "2") (pinfunction "CH1_2") (pintype "passive"))
    )
    (net (code "77") (name "Net-(U3-CH2)") (class "Default")
      (node (ref "R31") (pin "1") (pinfunction "1_1") (pintype "passive"))
      (node (ref "S21") (pin "1") (pinfunction "A_1") (pintype "passive"))
      (node (ref "S21") (pin "2") (pinfunction "A_2") (pintype "passive"))
      (node (ref "U3") (pin "3") (pinfunction "CH2_3") (pintype "passive"))
    )
    (net (code "78") (name "Net-(U3-CH3)") (class "Default")
      (node (ref "R32") (pin "1") (pinfunction "1_1") (pintype "passive"))
      (node (ref "S20") (pin "1") (pinfunction "A_1") (pintype "passive"))
      (node (ref "S20") (pin "2") (pinfunction "A_2") (pintype "passive"))
      (node (ref "U3") (pin "4") (pinfunction "CH3_4") (pintype "passive"))
    )
    (net (code "79") (name "Net-(U3-CH4)") (class "Default")
      (node (ref "R33") (pin "1") (pinfunction "1_1") (pintype "passive"))
      (node (ref "S19") (pin "1") (pinfunction "A_1") (pintype "passive"))
      (node (ref "S19") (pin "2") (pinfunction "A_2") (pintype "passive"))
      (node (ref "U3") (pin "5") (pinfunction "CH4_5") (pintype "passive"))
    )
    (net (code "80") (name "Net-(U3-CH5)") (class "Default")
      (node (ref "R34") (pin "1") (pinfunction "1_1") (pintype "passive"))
      (node (ref "S18") (pin "1") (pinfunction "A_1") (pintype "passive"))
      (node (ref "S18") (pin "2") (pinfunction "A_2") (pintype "passive"))
      (node (ref "U3") (pin "6") (pinfunction "CH5_6") (pintype "passive"))
    )
    (net (code "81") (name "Net-(U3-CH6)") (class "Default")
      (node (ref "R35") (pin "1") (pinfunction "1_1") (pintype "passive"))
      (node (ref "S17") (pin "1") (pinfunction "A_1") (pintype "passive"))
      (node (ref "S17") (pin "2") (pinfunction "A_2") (pintype "passive"))
      (node (ref "U3") (pin "7") (pinfunction "CH6_7") (pintype "passive"))
    )
    (net (code "82") (name "Net-(U3-CH7)") (class "Default")
      (node (ref "R36") (pin "1") (pinfunction "1_1") (pintype "passive"))
      (node (ref "S16") (pin "1") (pinfunction "A_1") (pintype "passive"))
      (node (ref "S16") (pin "2") (pinfunction "A_2") (pintype "passive"))
      (node (ref "U3") (pin "8") (pinfunction "CH7_8") (pintype "passive"))
    )
    (net (code "83") (name "VCC12_IN") (class "Default")
      (node (ref "ACCUM") (pin "2") (pinfunction "2_2") (pintype "passive"))
      (node (ref "Q1") (pin "3") (pinfunction "S_3") (pintype "passive"))
      (node (ref "R26") (pin "2") (pinfunction "2_2") (pintype "passive"))
      (node (ref "R27") (pin "2") (pinfunction "2_2") (pintype "passive"))
      (node (ref "T1") (pin "LCP") (pinfunction "P2_LCP") (pintype "passive"))
    )
    (net (code "84") (name "unconnected-(ESP-8266-GPIO0-Pad3)") (class "Default")
      (node (ref "ESP-8266") (pin "3") (pinfunction "GPIO0_3") (pintype "passive"))
    )
    (net (code "85") (name "unconnected-(ESP-8266-GPIO2-Pad2)") (class "Default")
      (node (ref "ESP-8266") (pin "2") (pinfunction "GPIO2_2") (pintype "passive"))
    )
    (net (code "86") (name "unconnected-(ESP-8266-GPIO16-Pad7)") (class "Default")
      (node (ref "ESP-8266") (pin "7") (pinfunction "GPIO16_7") (pintype "passive"))
    )
    (net (code "87") (name "unconnected-(J2-DAT1-Pad8)") (class "Default")
      (node (ref "J2") (pin "8") (pinfunction "DAT1_8") (pintype "passive"))
    )
    (net (code "88") (name "unconnected-(J2-DAT2-Pad1)") (class "Default")
      (node (ref "J2") (pin "1") (pinfunction "DAT2_1") (pintype "passive"))
    )
    (net (code "89") (name "unconnected-(J2-PadMP3)") (class "Default")
      (node (ref "J2") (pin "MP3") (pinfunction "MP3_MP3") (pintype "passive"))
    )
    (net (code "90") (name "unconnected-(LCD-MODULE-NC-Pad23)") (class "Default")
      (node (ref "LCD-MODULE") (pin "23") (pinfunction "NC_23") (pintype "passive"))
    )
    (net (code "91") (name "unconnected-(LCD-MODULE-NC-Pad24)") (class "Default")
      (node (ref "LCD-MODULE") (pin "24") (pinfunction "NC_24") (pintype "passive"))
    )
    (net (code "92") (name "unconnected-(LCD-MODULE-NC-Pad25)") (class "Default")
      (node (ref "LCD-MODULE") (pin "25") (pinfunction "NC_25") (pintype "passive"))
    )
    (net (code "93") (name "unconnected-(LCD-MODULE-NC-Pad27)") (class "Default")
      (node (ref "LCD-MODULE") (pin "27") (pinfunction "NC_27") (pintype "passive"))
    )
    (net (code "94") (name "unconnected-(LCD-MODULE-NC-Pad28)") (class "Default")
      (node (ref "LCD-MODULE") (pin "28") (pinfunction "NC_28") (pintype "passive"))
    )
    (net (code "95") (name "unconnected-(LCD-MODULE-NC-Pad29)") (class "Default")
      (node (ref "LCD-MODULE") (pin "29") (pinfunction "NC_29") (pintype "passive"))
    )
    (net (code "96") (name "unconnected-(LCD-MODULE-NC-Pad30)") (class "Default")
      (node (ref "LCD-MODULE") (pin "30") (pinfunction "NC_30") (pintype "passive"))
    )
    (net (code "97") (name "unconnected-(LCD-MODULE-RESET-Pad37)") (class "Default")
      (node (ref "LCD-MODULE") (pin "37") (pinfunction "RESET_37") (pintype "passive"))
    )
    (net (code "98") (name "unconnected-(LCD-MODULE-SD_CLK-Pad33)") (class "Default")
      (node (ref "LCD-MODULE") (pin "33") (pinfunction "SD_CLK_33") (pintype "passive"))
    )
    (net (code "99") (name "unconnected-(LCD-MODULE-SD_CS-Pad34)") (class "Default")
      (node (ref "LCD-MODULE") (pin "34") (pinfunction "SD_CS_34") (pintype "passive"))
    )
    (net (code "100") (name "unconnected-(LCD-MODULE-SD_MISO-Pad31)") (class "Default")
      (node (ref "LCD-MODULE") (pin "31") (pinfunction "SD_MISO_31") (pintype "passive"))
    )
    (net (code "101") (name "unconnected-(LCD-MODULE-SD_MOSI-Pad32)") (class "Default")
      (node (ref "LCD-MODULE") (pin "32") (pinfunction "SD_MOSI_32") (pintype "passive"))
    )
  )
)
